# 11_-EMMC_Chip.net
KiCad netlist of a schematic drawn in Altium Designer
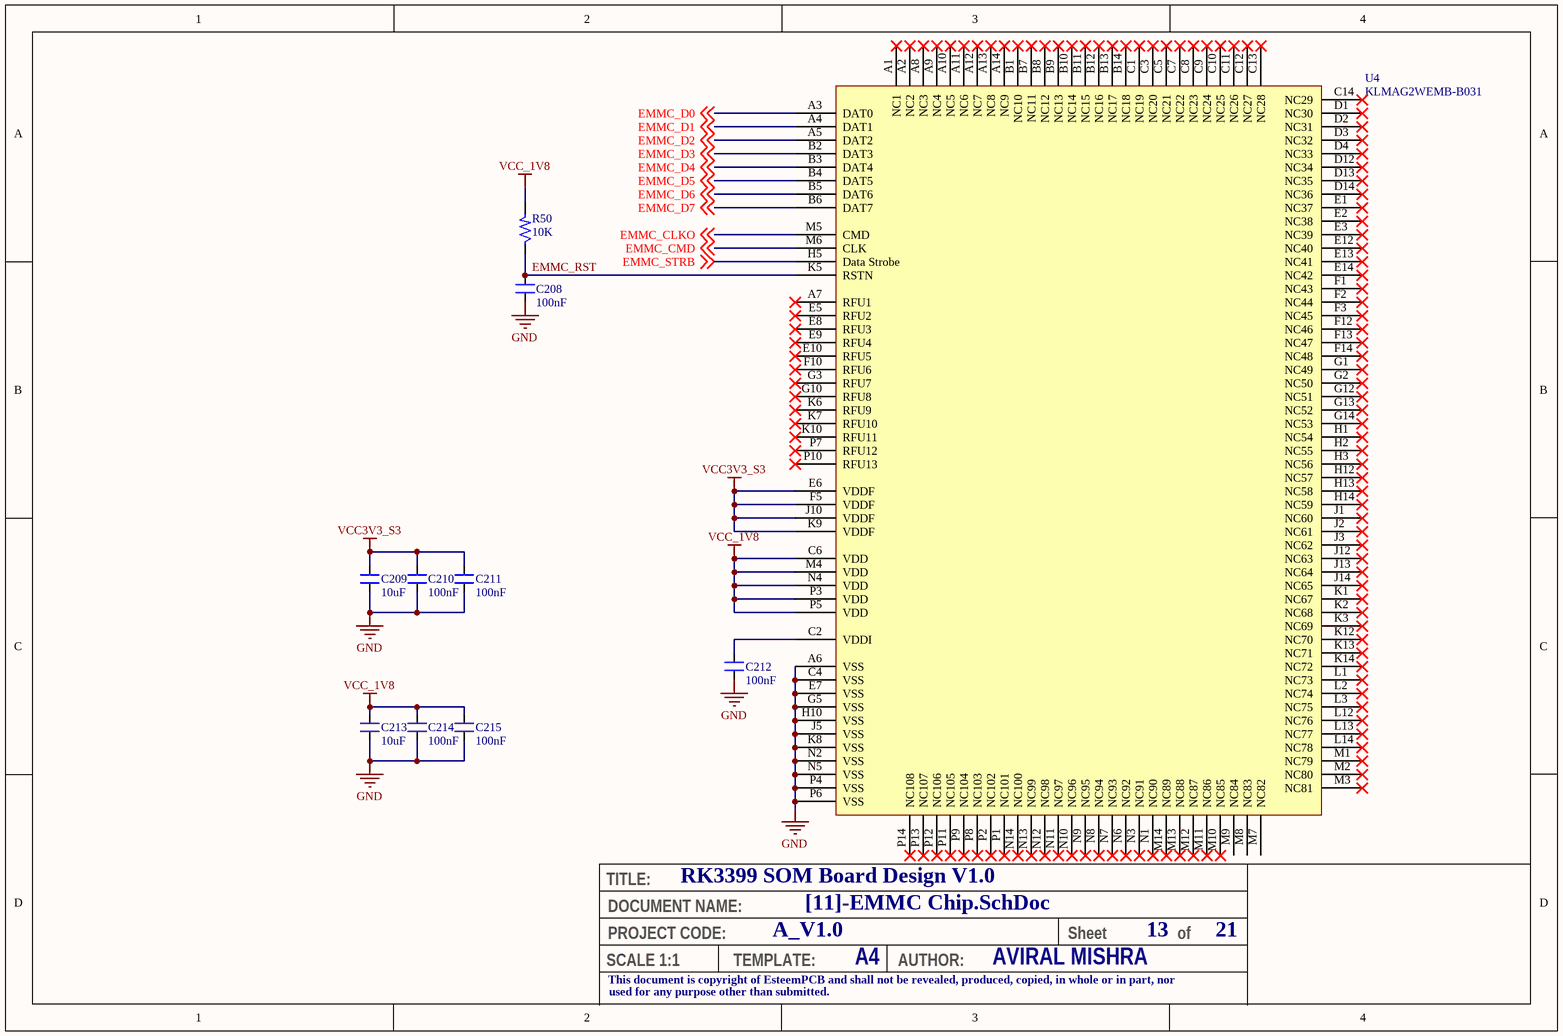
[diagram p0: [11]-EMMC Chip.SchDoc]

(export (version "E")
  (design (tool "Eeschema 10.0.6"))
  (components
    (comp (ref "C208")
      (value "100nF")
      (footprint "CAP_0201")
      (description "0.1µF ±10% 25V Ceramic Capacitor X5R 0201 (0603 Metric)")
      (fields
        (field (name "MANUFACTURER") "TDK Corporation")
        (field (name "MANUFACTURER PART NUMBER") "C0603X5R1E104K030BB")
      )
      (libsource (lib "EsteemPCB_SOM_Course_intlib") (part "CAP_100nF-25V-10%-0201"))
    )
    (comp (ref "C209")
      (value "10uF")
      (footprint "CAP_0603")
      (description "10µF ±10% 10V Ceramic Capacitor X5R 0603 (1608 Metric)")
      (fields
        (field (name "MANUFACTURER PART NUMBER") "GRM188R61A106KE69J")
        (field (name "MANUFACTURER") "Murata Electronics")
      )
      (libsource (lib "EsteemPCB_SOM_Course_intlib") (part "CAP_10uF-10V-10%-0603"))
    )
    (comp (ref "C210")
      (value "100nF")
      (footprint "CAP_0201")
      (description "0.1µF ±10% 25V Ceramic Capacitor X5R 0201 (0603 Metric)")
      (fields
        (field (name "MANUFACTURER") "TDK Corporation")
        (field (name "MANUFACTURER PART NUMBER") "C0603X5R1E104K030BB")
      )
      (libsource (lib "EsteemPCB_SOM_Course_intlib") (part "CAP_100nF-25V-10%-0201"))
    )
    (comp (ref "C211")
      (value "100nF")
      (footprint "CAP_0201")
      (description "0.1µF ±10% 25V Ceramic Capacitor X5R 0201 (0603 Metric)")
      (fields
        (field (name "MANUFACTURER") "TDK Corporation")
        (field (name "MANUFACTURER PART NUMBER") "C0603X5R1E104K030BB")
      )
      (libsource (lib "EsteemPCB_SOM_Course_intlib") (part "CAP_100nF-25V-10%-0201"))
    )
    (comp (ref "C212")
      (value "100nF")
      (footprint "CAP_0201")
      (description "0.1µF ±10% 25V Ceramic Capacitor X5R 0201 (0603 Metric)")
      (fields
        (field (name "MANUFACTURER") "TDK Corporation")
        (field (name "MANUFACTURER PART NUMBER") "C0603X5R1E104K030BB")
      )
      (libsource (lib "EsteemPCB_SOM_Course_intlib") (part "CAP_100nF-25V-10%-0201"))
    )
    (comp (ref "C213")
      (value "10uF")
      (footprint "CAP_0603")
      (description "10µF ±10% 10V Ceramic Capacitor X5R 0603 (1608 Metric)")
      (fields
        (field (name "MANUFACTURER PART NUMBER") "GRM188R61A106KE69J")
        (field (name "MANUFACTURER") "Murata Electronics")
      )
      (libsource (lib "EsteemPCB_SOM_Course_intlib") (part "CAP_10uF-10V-10%-0603"))
    )
    (comp (ref "C214")
      (value "100nF")
      (footprint "CAP_0201")
      (description "0.1µF ±10% 25V Ceramic Capacitor X5R 0201 (0603 Metric)")
      (fields
        (field (name "MANUFACTURER") "TDK Corporation")
        (field (name "MANUFACTURER PART NUMBER") "C0603X5R1E104K030BB")
      )
      (libsource (lib "EsteemPCB_SOM_Course_intlib") (part "CAP_100nF-25V-10%-0201"))
    )
    (comp (ref "C215")
      (value "100nF")
      (footprint "CAP_0201")
      (description "0.1µF ±10% 25V Ceramic Capacitor X5R 0201 (0603 Metric)")
      (fields
        (field (name "MANUFACTURER") "TDK Corporation")
        (field (name "MANUFACTURER PART NUMBER") "C0603X5R1E104K030BB")
      )
      (libsource (lib "EsteemPCB_SOM_Course_intlib") (part "CAP_100nF-25V-10%-0201"))
    )
    (comp (ref "R50")
      (value "10K")
      (footprint "RES_0201")
      (description "10 kOhms ±1% 0.05W, 1/20W Chip Resistor 0201 (0603 Metric) Thick Film")
      (fields
        (field (name "MANUFACTURER") "Stackpole Electronics Inc")
        (field (name "MANUFACTURER PART NUMBER") "RMCF0201FT10K0")
      )
      (libsource (lib "EsteemPCB_SOM_Course_intlib") (part "RES_10K-0.05W-1%-0201"))
    )
    (comp (ref "U4")
      (value "KLMAG2WEMB-B031")
      (footprint "BGA153C50P14X14_1150X1300X70")
      (description "16GB NAND Flash Memory")
      (fields (field (name "MANUFACTURER") "Samsung Electronics"))
      (libsource (lib "EsteemPCB_SOM_Course_intlib") (part "IC_KLMAG2WEMB-B031"))
    )
  )
  (nets
    (net (code "1") (name "/EMMC_RST") (class "Default")
      (node (ref "C208") (pin "2") (pinfunction "2_2") (pintype "passive"))
      (node (ref "R50") (pin "1") (pinfunction "1_1") (pintype "passive"))
      (node (ref "U4") (pin "K5") (pinfunction "RSTN_K5") (pintype "passive"))
    )
    (net (code "2") (name "EMMC_CLKO") (class "Default")
      (node (ref "U4") (pin "M5") (pinfunction "CMD_M5") (pintype "passive"))
    )
    (net (code "3") (name "EMMC_CMD") (class "Default")
      (node (ref "U4") (pin "M6") (pinfunction "CLK_M6") (pintype "passive"))
    )
    (net (code "4") (name "EMMC_D0") (class "Default")
      (node (ref "U4") (pin "A3") (pinfunction "DAT0_A3") (pintype "passive"))
    )
    (net (code "5") (name "EMMC_D1") (class "Default")
      (node (ref "U4") (pin "A4") (pinfunction "DAT1_A4") (pintype "passive"))
    )
    (net (code "6") (name "EMMC_D2") (class "Default")
      (node (ref "U4") (pin "A5") (pinfunction "DAT2_A5") (pintype "passive"))
    )
    (net (code "7") (name "EMMC_D3") (class "Default")
      (node (ref "U4") (pin "B2") (pinfunction "DAT3_B2") (pintype "passive"))
    )
    (net (code "8") (name "EMMC_D4") (class "Default")
      (node (ref "U4") (pin "B3") (pinfunction "DAT4_B3") (pintype "passive"))
    )
    (net (code "9") (name "EMMC_D5") (class "Default")
      (node (ref "U4") (pin "B4") (pinfunction "DAT5_B4") (pintype "passive"))
    )
    (net (code "10") (name "EMMC_D6") (class "Default")
      (node (ref "U4") (pin "B5") (pinfunction "DAT6_B5") (pintype "passive"))
    )
    (net (code "11") (name "EMMC_D7") (class "Default")
      (node (ref "U4") (pin "B6") (pinfunction "DAT7_B6") (pintype "passive"))
    )
    (net (code "12") (name "EMMC_STRB") (class "Default")
      (node (ref "U4") (pin "H5") (pinfunction "Data_Strobe_H5") (pintype "passive"))
    )
    (net (code "13") (name "GND") (class "Default")
      (node (ref "C208") (pin "1") (pinfunction "1_1") (pintype "passive"))
      (node (ref "C209") (pin "1") (pinfunction "1_1") (pintype "passive"))
      (node (ref "C210") (pin "1") (pinfunction "1_1") (pintype "passive"))
      (node (ref "C211") (pin "1") (pinfunction "1_1") (pintype "passive"))
      (node (ref "C212") (pin "1") (pinfunction "1_1") (pintype "passive"))
      (node (ref "C213") (pin "1") (pinfunction "1_1") (pintype "passive"))
      (node (ref "C214") (pin "1") (pinfunction "1_1") (pintype "passive"))
      (node (ref "C215") (pin "1") (pinfunction "1_1") (pintype "passive"))
      (node (ref "U4") (pin "A6") (pinfunction "VSS_A6") (pintype "passive"))
      (node (ref "U4") (pin "C4") (pinfunction "VSS_C4") (pintype "passive"))
      (node (ref "U4") (pin "E7") (pinfunction "VSS_E7") (pintype "passive"))
      (node (ref "U4") (pin "G5") (pinfunction "VSS_G5") (pintype "passive"))
      (node (ref "U4") (pin "H10") (pinfunction "VSS_H10") (pintype "passive"))
      (node (ref "U4") (pin "J5") (pinfunction "VSS_J5") (pintype "passive"))
      (node (ref "U4") (pin "K8") (pinfunction "VSS_K8") (pintype "passive"))
      (node (ref "U4") (pin "N2") (pinfunction "VSS_N2") (pintype "passive"))
      (node (ref "U4") (pin "N5") (pinfunction "VSS_N5") (pintype "passive"))
      (node (ref "U4") (pin "P4") (pinfunction "VSS_P4") (pintype "passive"))
      (node (ref "U4") (pin "P6") (pinfunction "VSS_P6") (pintype "passive"))
    )
    (net (code "14") (name "Net-(U4-VDDI)") (class "Default")
      (node (ref "C212") (pin "2") (pinfunction "2_2") (pintype "passive"))
      (node (ref "U4") (pin "C2") (pinfunction "VDDI_C2") (pintype "passive"))
    )
    (net (code "15") (name "VCC3V3_S3") (class "Default")
      (node (ref "C209") (pin "2") (pinfunction "2_2") (pintype "passive"))
      (node (ref "C210") (pin "2") (pinfunction "2_2") (pintype "passive"))
      (node (ref "C211") (pin "2") (pinfunction "2_2") (pintype "passive"))
      (node (ref "U4") (pin "E6") (pinfunction "VDDF_E6") (pintype "passive"))
      (node (ref "U4") (pin "F5") (pinfunction "VDDF_F5") (pintype "passive"))
      (node (ref "U4") (pin "J10") (pinfunction "VDDF_J10") (pintype "passive"))
      (node (ref "U4") (pin "K9") (pinfunction "VDDF_K9") (pintype "passive"))
    )
    (net (code "16") (name "VCC_1V8") (class "Default")
      (node (ref "C213") (pin "2") (pinfunction "2_2") (pintype "passive"))
      (node (ref "C214") (pin "2") (pinfunction "2_2") (pintype "passive"))
      (node (ref "C215") (pin "2") (pinfunction "2_2") (pintype "passive"))
      (node (ref "R50") (pin "2") (pinfunction "2_2") (pintype "passive"))
      (node (ref "U4") (pin "C6") (pinfunction "VDD_C6") (pintype "passive"))
      (node (ref "U4") (pin "M4") (pinfunction "VDD_M4") (pintype "passive"))
      (node (ref "U4") (pin "N4") (pinfunction "VDD_N4") (pintype "passive"))
      (node (ref "U4") (pin "P3") (pinfunction "VDD_P3") (pintype "passive"))
      (node (ref "U4") (pin "P5") (pinfunction "VDD_P5") (pintype "passive"))
    )
    (net (code "17") (name "unconnected-(U4-NC1-PadA1)") (class "Default")
      (node (ref "U4") (pin "A1") (pinfunction "NC1_A1") (pintype "passive+no_connect"))
    )
    (net (code "18") (name "unconnected-(U4-NC2-PadA2)") (class "Default")
      (node (ref "U4") (pin "A2") (pinfunction "NC2_A2") (pintype "passive+no_connect"))
    )
    (net (code "19") (name "unconnected-(U4-NC3-PadA8)") (class "Default")
      (node (ref "U4") (pin "A8") (pinfunction "NC3_A8") (pintype "passive+no_connect"))
    )
    (net (code "20") (name "unconnected-(U4-NC4-PadA9)") (class "Default")
      (node (ref "U4") (pin "A9") (pinfunction "NC4_A9") (pintype "passive+no_connect"))
    )
    (net (code "21") (name "unconnected-(U4-NC5-PadA10)") (class "Default")
      (node (ref "U4") (pin "A10") (pinfunction "NC5_A10") (pintype "passive+no_connect"))
    )
    (net (code "22") (name "unconnected-(U4-NC6-PadA11)") (class "Default")
      (node (ref "U4") (pin "A11") (pinfunction "NC6_A11") (pintype "passive+no_connect"))
    )
    (net (code "23") (name "unconnected-(U4-NC7-PadA12)") (class "Default")
      (node (ref "U4") (pin "A12") (pinfunction "NC7_A12") (pintype "passive+no_connect"))
    )
    (net (code "24") (name "unconnected-(U4-NC8-PadA13)") (class "Default")
      (node (ref "U4") (pin "A13") (pinfunction "NC8_A13") (pintype "passive+no_connect"))
    )
    (net (code "25") (name "unconnected-(U4-NC9-PadA14)") (class "Default")
      (node (ref "U4") (pin "A14") (pinfunction "NC9_A14") (pintype "passive+no_connect"))
    )
    (net (code "26") (name "unconnected-(U4-NC10-PadB1)") (class "Default")
      (node (ref "U4") (pin "B1") (pinfunction "NC10_B1") (pintype "passive+no_connect"))
    )
    (net (code "27") (name "unconnected-(U4-NC11-PadB7)") (class "Default")
      (node (ref "U4") (pin "B7") (pinfunction "NC11_B7") (pintype "passive+no_connect"))
    )
    (net (code "28") (name "unconnected-(U4-NC12-PadB8)") (class "Default")
      (node (ref "U4") (pin "B8") (pinfunction "NC12_B8") (pintype "passive+no_connect"))
    )
    (net (code "29") (name "unconnected-(U4-NC13-PadB9)") (class "Default")
      (node (ref "U4") (pin "B9") (pinfunction "NC13_B9") (pintype "passive+no_connect"))
    )
    (net (code "30") (name "unconnected-(U4-NC14-PadB10)") (class "Default")
      (node (ref "U4") (pin "B10") (pinfunction "NC14_B10") (pintype "passive+no_connect"))
    )
    (net (code "31") (name "unconnected-(U4-NC15-PadB11)") (class "Default")
      (node (ref "U4") (pin "B11") (pinfunction "NC15_B11") (pintype "passive+no_connect"))
    )
    (net (code "32") (name "unconnected-(U4-NC16-PadB12)") (class "Default")
      (node (ref "U4") (pin "B12") (pinfunction "NC16_B12") (pintype "passive+no_connect"))
    )
    (net (code "33") (name "unconnected-(U4-NC17-PadB13)") (class "Default")
      (node (ref "U4") (pin "B13") (pinfunction "NC17_B13") (pintype "passive+no_connect"))
    )
    (net (code "34") (name "unconnected-(U4-NC18-PadB14)") (class "Default")
      (node (ref "U4") (pin "B14") (pinfunction "NC18_B14") (pintype "passive+no_connect"))
    )
    (net (code "35") (name "unconnected-(U4-NC19-PadC1)") (class "Default")
      (node (ref "U4") (pin "C1") (pinfunction "NC19_C1") (pintype "passive+no_connect"))
    )
    (net (code "36") (name "unconnected-(U4-NC20-PadC3)") (class "Default")
      (node (ref "U4") (pin "C3") (pinfunction "NC20_C3") (pintype "passive+no_connect"))
    )
    (net (code "37") (name "unconnected-(U4-NC21-PadC5)") (class "Default")
      (node (ref "U4") (pin "C5") (pinfunction "NC21_C5") (pintype "passive+no_connect"))
    )
    (net (code "38") (name "unconnected-(U4-NC22-PadC7)") (class "Default")
      (node (ref "U4") (pin "C7") (pinfunction "NC22_C7") (pintype "passive+no_connect"))
    )
    (net (code "39") (name "unconnected-(U4-NC23-PadC8)") (class "Default")
      (node (ref "U4") (pin "C8") (pinfunction "NC23_C8") (pintype "passive+no_connect"))
    )
    (net (code "40") (name "unconnected-(U4-NC24-PadC9)") (class "Default")
      (node (ref "U4") (pin "C9") (pinfunction "NC24_C9") (pintype "passive+no_connect"))
    )
    (net (code "41") (name "unconnected-(U4-NC25-PadC10)") (class "Default")
      (node (ref "U4") (pin "C10") (pinfunction "NC25_C10") (pintype "passive+no_connect"))
    )
    (net (code "42") (name "unconnected-(U4-NC26-PadC11)") (class "Default")
      (node (ref "U4") (pin "C11") (pinfunction "NC26_C11") (pintype "passive+no_connect"))
    )
    (net (code "43") (name "unconnected-(U4-NC27-PadC12)") (class "Default")
      (node (ref "U4") (pin "C12") (pinfunction "NC27_C12") (pintype "passive+no_connect"))
    )
    (net (code "44") (name "unconnected-(U4-NC28-PadC13)") (class "Default")
      (node (ref "U4") (pin "C13") (pinfunction "NC28_C13") (pintype "passive+no_connect"))
    )
    (net (code "45") (name "unconnected-(U4-NC29-PadC14)") (class "Default")
      (node (ref "U4") (pin "C14") (pinfunction "NC29_C14") (pintype "passive+no_connect"))
    )
    (net (code "46") (name "unconnected-(U4-NC30-PadD1)") (class "Default")
      (node (ref "U4") (pin "D1") (pinfunction "NC30_D1") (pintype "passive+no_connect"))
    )
    (net (code "47") (name "unconnected-(U4-NC31-PadD2)") (class "Default")
      (node (ref "U4") (pin "D2") (pinfunction "NC31_D2") (pintype "passive+no_connect"))
    )
    (net (code "48") (name "unconnected-(U4-NC32-PadD3)") (class "Default")
      (node (ref "U4") (pin "D3") (pinfunction "NC32_D3") (pintype "passive+no_connect"))
    )
    (net (code "49") (name "unconnected-(U4-NC33-PadD4)") (class "Default")
      (node (ref "U4") (pin "D4") (pinfunction "NC33_D4") (pintype "passive+no_connect"))
    )
    (net (code "50") (name "unconnected-(U4-NC34-PadD12)") (class "Default")
      (node (ref "U4") (pin "D12") (pinfunction "NC34_D12") (pintype "passive+no_connect"))
    )
    (net (code "51") (name "unconnected-(U4-NC35-PadD13)") (class "Default")
      (node (ref "U4") (pin "D13") (pinfunction "NC35_D13") (pintype "passive+no_connect"))
    )
    (net (code "52") (name "unconnected-(U4-NC36-PadD14)") (class "Default")
      (node (ref "U4") (pin "D14") (pinfunction "NC36_D14") (pintype "passive+no_connect"))
    )
    (net (code "53") (name "unconnected-(U4-NC37-PadE1)") (class "Default")
      (node (ref "U4") (pin "E1") (pinfunction "NC37_E1") (pintype "passive+no_connect"))
    )
    (net (code "54") (name "unconnected-(U4-NC38-PadE2)") (class "Default")
      (node (ref "U4") (pin "E2") (pinfunction "NC38_E2") (pintype "passive+no_connect"))
    )
    (net (code "55") (name "unconnected-(U4-NC39-PadE3)") (class "Default")
      (node (ref "U4") (pin "E3") (pinfunction "NC39_E3") (pintype "passive+no_connect"))
    )
    (net (code "56") (name "unconnected-(U4-NC40-PadE12)") (class "Default")
      (node (ref "U4") (pin "E12") (pinfunction "NC40_E12") (pintype "passive+no_connect"))
    )
    (net (code "57") (name "unconnected-(U4-NC41-PadE13)") (class "Default")
      (node (ref "U4") (pin "E13") (pinfunction "NC41_E13") (pintype "passive+no_connect"))
    )
    (net (code "58") (name "unconnected-(U4-NC42-PadE14)") (class "Default")
      (node (ref "U4") (pin "E14") (pinfunction "NC42_E14") (pintype "passive+no_connect"))
    )
    (net (code "59") (name "unconnected-(U4-NC43-PadF1)") (class "Default")
      (node (ref "U4") (pin "F1") (pinfunction "NC43_F1") (pintype "passive+no_connect"))
    )
    (net (code "60") (name "unconnected-(U4-NC44-PadF2)") (class "Default")
      (node (ref "U4") (pin "F2") (pinfunction "NC44_F2") (pintype "passive+no_connect"))
    )
    (net (code "61") (name "unconnected-(U4-NC45-PadF3)") (class "Default")
      (node (ref "U4") (pin "F3") (pinfunction "NC45_F3") (pintype "passive+no_connect"))
    )
    (net (code "62") (name "unconnected-(U4-NC46-PadF12)") (class "Default")
      (node (ref "U4") (pin "F12") (pinfunction "NC46_F12") (pintype "passive+no_connect"))
    )
    (net (code "63") (name "unconnected-(U4-NC47-PadF13)") (class "Default")
      (node (ref "U4") (pin "F13") (pinfunction "NC47_F13") (pintype "passive+no_connect"))
    )
    (net (code "64") (name "unconnected-(U4-NC48-PadF14)") (class "Default")
      (node (ref "U4") (pin "F14") (pinfunction "NC48_F14") (pintype "passive+no_connect"))
    )
    (net (code "65") (name "unconnected-(U4-NC49-PadG1)") (class "Default")
      (node (ref "U4") (pin "G1") (pinfunction "NC49_G1") (pintype "passive+no_connect"))
    )
    (net (code "66") (name "unconnected-(U4-NC50-PadG2)") (class "Default")
      (node (ref "U4") (pin "G2") (pinfunction "NC50_G2") (pintype "passive+no_connect"))
    )
    (net (code "67") (name "unconnected-(U4-NC51-PadG12)") (class "Default")
      (node (ref "U4") (pin "G12") (pinfunction "NC51_G12") (pintype "passive+no_connect"))
    )
    (net (code "68") (name "unconnected-(U4-NC52-PadG13)") (class "Default")
      (node (ref "U4") (pin "G13") (pinfunction "NC52_G13") (pintype "passive+no_connect"))
    )
    (net (code "69") (name "unconnected-(U4-NC53-PadG14)") (class "Default")
      (node (ref "U4") (pin "G14") (pinfunction "NC53_G14") (pintype "passive+no_connect"))
    )
    (net (code "70") (name "unconnected-(U4-NC54-PadH1)") (class "Default")
      (node (ref "U4") (pin "H1") (pinfunction "NC54_H1") (pintype "passive+no_connect"))
    )
    (net (code "71") (name "unconnected-(U4-NC55-PadH2)") (class "Default")
      (node (ref "U4") (pin "H2") (pinfunction "NC55_H2") (pintype "passive+no_connect"))
    )
    (net (code "72") (name "unconnected-(U4-NC56-PadH3)") (class "Default")
      (node (ref "U4") (pin "H3") (pinfunction "NC56_H3") (pintype "passive+no_connect"))
    )
    (net (code "73") (name "unconnected-(U4-NC57-PadH12)") (class "Default")
      (node (ref "U4") (pin "H12") (pinfunction "NC57_H12") (pintype "passive+no_connect"))
    )
    (net (code "74") (name "unconnected-(U4-NC58-PadH13)") (class "Default")
      (node (ref "U4") (pin "H13") (pinfunction "NC58_H13") (pintype "passive+no_connect"))
    )
    (net (code "75") (name "unconnected-(U4-NC59-PadH14)") (class "Default")
      (node (ref "U4") (pin "H14") (pinfunction "NC59_H14") (pintype "passive+no_connect"))
    )
    (net (code "76") (name "unconnected-(U4-NC60-PadJ1)") (class "Default")
      (node (ref "U4") (pin "J1") (pinfunction "NC60_J1") (pintype "passive+no_connect"))
    )
    (net (code "77") (name "unconnected-(U4-NC61-PadJ2)") (class "Default")
      (node (ref "U4") (pin "J2") (pinfunction "NC61_J2") (pintype "passive+no_connect"))
    )
    (net (code "78") (name "unconnected-(U4-NC62-PadJ3)") (class "Default")
      (node (ref "U4") (pin "J3") (pinfunction "NC62_J3") (pintype "passive+no_connect"))
    )
    (net (code "79") (name "unconnected-(U4-NC63-PadJ12)") (class "Default")
      (node (ref "U4") (pin "J12") (pinfunction "NC63_J12") (pintype "passive+no_connect"))
    )
    (net (code "80") (name "unconnected-(U4-NC64-PadJ13)") (class "Default")
      (node (ref "U4") (pin "J13") (pinfunction "NC64_J13") (pintype "passive+no_connect"))
    )
    (net (code "81") (name "unconnected-(U4-NC65-PadJ14)") (class "Default")
      (node (ref "U4") (pin "J14") (pinfunction "NC65_J14") (pintype "passive+no_connect"))
    )
    (net (code "82") (name "unconnected-(U4-NC67-PadK1)") (class "Default")
      (node (ref "U4") (pin "K1") (pinfunction "NC67_K1") (pintype "passive+no_connect"))
    )
    (net (code "83") (name "unconnected-(U4-NC68-PadK2)") (class "Default")
      (node (ref "U4") (pin "K2") (pinfunction "NC68_K2") (pintype "passive+no_connect"))
    )
    (net (code "84") (name "unconnected-(U4-NC69-PadK3)") (class "Default")
      (node (ref "U4") (pin "K3") (pinfunction "NC69_K3") (pintype "passive+no_connect"))
    )
    (net (code "85") (name "unconnected-(U4-NC70-PadK12)") (class "Default")
      (node (ref "U4") (pin "K12") (pinfunction "NC70_K12") (pintype "passive+no_connect"))
    )
    (net (code "86") (name "unconnected-(U4-NC71-PadK13)") (class "Default")
      (node (ref "U4") (pin "K13") (pinfunction "NC71_K13") (pintype "passive+no_connect"))
    )
    (net (code "87") (name "unconnected-(U4-NC72-PadK14)") (class "Default")
      (node (ref "U4") (pin "K14") (pinfunction "NC72_K14") (pintype "passive+no_connect"))
    )
    (net (code "88") (name "unconnected-(U4-NC73-PadL1)") (class "Default")
      (node (ref "U4") (pin "L1") (pinfunction "NC73_L1") (pintype "passive+no_connect"))
    )
    (net (code "89") (name "unconnected-(U4-NC74-PadL2)") (class "Default")
      (node (ref "U4") (pin "L2") (pinfunction "NC74_L2") (pintype "passive+no_connect"))
    )
    (net (code "90") (name "unconnected-(U4-NC75-PadL3)") (class "Default")
      (node (ref "U4") (pin "L3") (pinfunction "NC75_L3") (pintype "passive+no_connect"))
    )
    (net (code "91") (name "unconnected-(U4-NC76-PadL12)") (class "Default")
      (node (ref "U4") (pin "L12") (pinfunction "NC76_L12") (pintype "passive+no_connect"))
    )
    (net (code "92") (name "unconnected-(U4-NC77-PadL13)") (class "Default")
      (node (ref "U4") (pin "L13") (pinfunction "NC77_L13") (pintype "passive+no_connect"))
    )
    (net (code "93") (name "unconnected-(U4-NC78-PadL14)") (class "Default")
      (node (ref "U4") (pin "L14") (pinfunction "NC78_L14") (pintype "passive+no_connect"))
    )
    (net (code "94") (name "unconnected-(U4-NC79-PadM1)") (class "Default")
      (node (ref "U4") (pin "M1") (pinfunction "NC79_M1") (pintype "passive+no_connect"))
    )
    (net (code "95") (name "unconnected-(U4-NC80-PadM2)") (class "Default")
      (node (ref "U4") (pin "M2") (pinfunction "NC80_M2") (pintype "passive+no_connect"))
    )
    (net (code "96") (name "unconnected-(U4-NC81-PadM3)") (class "Default")
      (node (ref "U4") (pin "M3") (pinfunction "NC81_M3") (pintype "passive+no_connect"))
    )
    (net (code "97") (name "unconnected-(U4-NC82-PadM7)") (class "Default")
      (node (ref "U4") (pin "M7") (pinfunction "NC82_M7") (pintype "passive"))
    )
    (net (code "98") (name "unconnected-(U4-NC83-PadM8)") (class "Default")
      (node (ref "U4") (pin "M8") (pinfunction "NC83_M8") (pintype "passive"))
    )
    (net (code "99") (name "unconnected-(U4-NC84-PadM9)") (class "Default")
      (node (ref "U4") (pin "M9") (pinfunction "NC84_M9") (pintype "passive"))
    )
    (net (code "100") (name "unconnected-(U4-NC85-PadM10)") (class "Default")
      (node (ref "U4") (pin "M10") (pinfunction "NC85_M10") (pintype "passive+no_connect"))
    )
    (net (code "101") (name "unconnected-(U4-NC86-PadM11)") (class "Default")
      (node (ref "U4") (pin "M11") (pinfunction "NC86_M11") (pintype "passive+no_connect"))
    )
    (net (code "102") (name "unconnected-(U4-NC87-PadM12)") (class "Default")
      (node (ref "U4") (pin "M12") (pinfunction "NC87_M12") (pintype "passive+no_connect"))
    )
    (net (code "103") (name "unconnected-(U4-NC88-PadM13)") (class "Default")
      (node (ref "U4") (pin "M13") (pinfunction "NC88_M13") (pintype "passive+no_connect"))
    )
    (net (code "104") (name "unconnected-(U4-NC89-PadM14)") (class "Default")
      (node (ref "U4") (pin "M14") (pinfunction "NC89_M14") (pintype "passive+no_connect"))
    )
    (net (code "105") (name "unconnected-(U4-NC90-PadN1)") (class "Default")
      (node (ref "U4") (pin "N1") (pinfunction "NC90_N1") (pintype "passive+no_connect"))
    )
    (net (code "106") (name "unconnected-(U4-NC91-PadN3)") (class "Default")
      (node (ref "U4") (pin "N3") (pinfunction "NC91_N3") (pintype "passive+no_connect"))
    )
    (net (code "107") (name "unconnected-(U4-NC92-PadN6)") (class "Default")
      (node (ref "U4") (pin "N6") (pinfunction "NC92_N6") (pintype "passive+no_connect"))
    )
    (net (code "108") (name "unconnected-(U4-NC93-PadN7)") (class "Default")
      (node (ref "U4") (pin "N7") (pinfunction "NC93_N7") (pintype "passive+no_connect"))
    )
    (net (code "109") (name "unconnected-(U4-NC94-PadN8)") (class "Default")
      (node (ref "U4") (pin "N8") (pinfunction "NC94_N8") (pintype "passive+no_connect"))
    )
    (net (code "110") (name "unconnected-(U4-NC95-PadN9)") (class "Default")
      (node (ref "U4") (pin "N9") (pinfunction "NC95_N9") (pintype "passive+no_connect"))
    )
    (net (code "111") (name "unconnected-(U4-NC96-PadN10)") (class "Default")
      (node (ref "U4") (pin "N10") (pinfunction "NC96_N10") (pintype "passive+no_connect"))
    )
    (net (code "112") (name "unconnected-(U4-NC97-PadN11)") (class "Default")
      (node (ref "U4") (pin "N11") (pinfunction "NC97_N11") (pintype "passive+no_connect"))
    )
    (net (code "113") (name "unconnected-(U4-NC98-PadN12)") (class "Default")
      (node (ref "U4") (pin "N12") (pinfunction "NC98_N12") (pintype "passive+no_connect"))
    )
    (net (code "114") (name "unconnected-(U4-NC99-PadN13)") (class "Default")
      (node (ref "U4") (pin "N13") (pinfunction "NC99_N13") (pintype "passive+no_connect"))
    )
    (net (code "115") (name "unconnected-(U4-NC100-PadN14)") (class "Default")
      (node (ref "U4") (pin "N14") (pinfunction "NC100_N14") (pintype "passive+no_connect"))
    )
    (net (code "116") (name "unconnected-(U4-NC101-PadP1)") (class "Default")
      (node (ref "U4") (pin "P1") (pinfunction "NC101_P1") (pintype "passive+no_connect"))
    )
    (net (code "117") (name "unconnected-(U4-NC102-PadP2)") (class "Default")
      (node (ref "U4") (pin "P2") (pinfunction "NC102_P2") (pintype "passive+no_connect"))
    )
    (net (code "118") (name "unconnected-(U4-NC103-PadP8)") (class "Default")
      (node (ref "U4") (pin "P8") (pinfunction "NC103_P8") (pintype "passive+no_connect"))
    )
    (net (code "119") (name "unconnected-(U4-NC104-PadP9)") (class "Default")
      (node (ref "U4") (pin "P9") (pinfunction "NC104_P9") (pintype "passive+no_connect"))
    )
    (net (code "120") (name "unconnected-(U4-NC105-PadP11)") (class "Default")
      (node (ref "U4") (pin "P11") (pinfunction "NC105_P11") (pintype "passive+no_connect"))
    )
    (net (code "121") (name "unconnected-(U4-NC106-PadP12)") (class "Default")
      (node (ref "U4") (pin "P12") (pinfunction "NC106_P12") (pintype "passive+no_connect"))
    )
    (net (code "122") (name "unconnected-(U4-NC107-PadP13)") (class "Default")
      (node (ref "U4") (pin "P13") (pinfunction "NC107_P13") (pintype "passive+no_connect"))
    )
    (net (code "123") (name "unconnected-(U4-NC108-PadP14)") (class "Default")
      (node (ref "U4") (pin "P14") (pinfunction "NC108_P14") (pintype "passive+no_connect"))
    )
    (net (code "124") (name "unconnected-(U4-RFU1-PadA7)") (class "Default")
      (node (ref "U4") (pin "A7") (pinfunction "RFU1_A7") (pintype "passive+no_connect"))
    )
    (net (code "125") (name "unconnected-(U4-RFU2-PadE5)") (class "Default")
      (node (ref "U4") (pin "E5") (pinfunction "RFU2_E5") (pintype "passive+no_connect"))
    )
    (net (code "126") (name "unconnected-(U4-RFU3-PadE8)") (class "Default")
      (node (ref "U4") (pin "E8") (pinfunction "RFU3_E8") (pintype "passive+no_connect"))
    )
    (net (code "127") (name "unconnected-(U4-RFU4-PadE9)") (class "Default")
      (node (ref "U4") (pin "E9") (pinfunction "RFU4_E9") (pintype "passive+no_connect"))
    )
    (net (code "128") (name "unconnected-(U4-RFU5-PadE10)") (class "Default")
      (node (ref "U4") (pin "E10") (pinfunction "RFU5_E10") (pintype "passive+no_connect"))
    )
    (net (code "129") (name "unconnected-(U4-RFU6-PadF10)") (class "Default")
      (node (ref "U4") (pin "F10") (pinfunction "RFU6_F10") (pintype "passive+no_connect"))
    )
    (net (code "130") (name "unconnected-(U4-RFU7-PadG3)") (class "Default")
      (node (ref "U4") (pin "G3") (pinfunction "RFU7_G3") (pintype "passive+no_connect"))
    )
    (net (code "131") (name "unconnected-(U4-RFU8-PadG10)") (class "Default")
      (node (ref "U4") (pin "G10") (pinfunction "RFU8_G10") (pintype "passive+no_connect"))
    )
    (net (code "132") (name "unconnected-(U4-RFU9-PadK6)") (class "Default")
      (node (ref "U4") (pin "K6") (pinfunction "RFU9_K6") (pintype "passive+no_connect"))
    )
    (net (code "133") (name "unconnected-(U4-RFU10-PadK7)") (class "Default")
      (node (ref "U4") (pin "K7") (pinfunction "RFU10_K7") (pintype "passive+no_connect"))
    )
    (net (code "134") (name "unconnected-(U4-RFU11-PadK10)") (class "Default")
      (node (ref "U4") (pin "K10") (pinfunction "RFU11_K10") (pintype "passive+no_connect"))
    )
    (net (code "135") (name "unconnected-(U4-RFU12-PadP7)") (class "Default")
      (node (ref "U4") (pin "P7") (pinfunction "RFU12_P7") (pintype "passive+no_connect"))
    )
    (net (code "136") (name "unconnected-(U4-RFU13-PadP10)") (class "Default")
      (node (ref "U4") (pin "P10") (pinfunction "RFU13_P10") (pintype "passive+no_connect"))
    )
  )
)
